# LightingUPS-AC.net
KiCad netlist of a schematic drawn in EAGLE
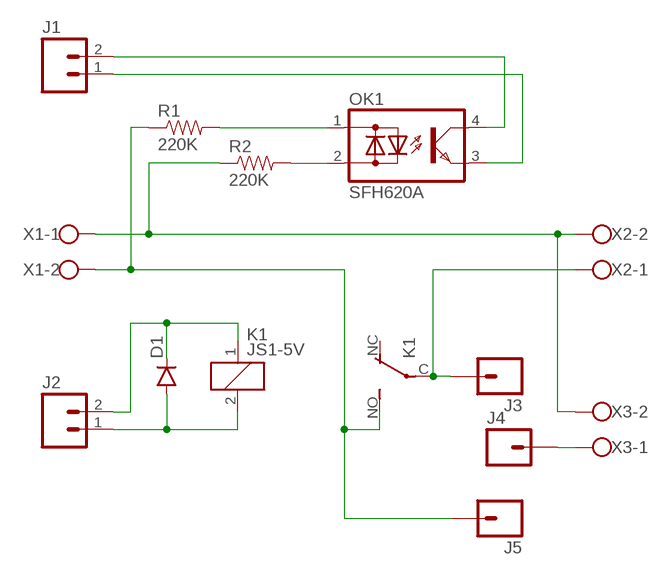
[diagram p0: schematic, sheet 1]

(export (version "E")
  (design (tool "Eeschema 10.0.6"))
  (components
    (comp (ref "D1")
      (value "DIODEPTH")
      (footprint "eagle-import:DIODE-1N4001")
      (libsource (lib "eagle-import") (part "DIODEPTH"))
    )
    (comp (ref "J1")
      (value "M02PTH")
      (footprint "eagle-import:1X02")
      (libsource (lib "eagle-import") (part "M02PTH"))
    )
    (comp (ref "J2")
      (value "M02PTH")
      (footprint "eagle-import:1X02")
      (libsource (lib "eagle-import") (part "M02PTH"))
    )
    (comp (ref "J3")
      (value "M01PTH")
      (footprint "eagle-import:1X01")
      (libsource (lib "eagle-import") (part "M01PTH"))
    )
    (comp (ref "J4")
      (value "M01PTH")
      (footprint "eagle-import:1X01")
      (libsource (lib "eagle-import") (part "M01PTH"))
    )
    (comp (ref "J5")
      (value "M01PTH")
      (footprint "eagle-import:1X01")
      (libsource (lib "eagle-import") (part "M01PTH"))
    )
    (comp (ref "K1")
      (value "JS1-5V")
      (footprint "eagle-import:JS-M")
      (libsource (lib "eagle-import") (part "JS-M1-9V-4"))
    )
    (comp (ref "OK1")
      (value "SFH620A")
      (footprint "eagle-import:DIL04")
      (fields (field (name "MPN") "SFH620A-2"))
      (libsource (lib "eagle-import") (part "SFH620A"))
    )
    (comp (ref "R1")
      (value "220K")
      (footprint "eagle-import:AXIAL-0.4")
      (libsource (lib "eagle-import") (part "RESISTORPTH-1/4W"))
    )
    (comp (ref "R2")
      (value "220K")
      (footprint "eagle-import:AXIAL-0.4")
      (libsource (lib "eagle-import") (part "RESISTORPTH-1/4W"))
    )
    (comp (ref "X1")
      (value "W237-102")
      (footprint "eagle-import:W237-102")
      (fields (field (name "MPN") "237-102"))
      (libsource (lib "eagle-import") (part "W237-102"))
    )
    (comp (ref "X2")
      (value "W237-102")
      (footprint "eagle-import:W237-102")
      (fields (field (name "MPN") "237-102"))
      (libsource (lib "eagle-import") (part "W237-102"))
    )
    (comp (ref "X3")
      (value "W237-102")
      (footprint "eagle-import:W237-102")
      (fields (field (name "MPN") "237-102"))
      (libsource (lib "eagle-import") (part "W237-102"))
    )
  )
  (nets
    (net (code "1") (name "Net-(D1-PadA)") (class "Default")
      (node (ref "D1") (pin "A") (pinfunction "A_A") (pintype "passive"))
      (node (ref "J2") (pin "1") (pinfunction "1_1") (pintype "passive"))
      (node (ref "K1") (pin "2") (pinfunction "2_2") (pintype "passive"))
    )
    (net (code "2") (name "Net-(D1-PadC)") (class "Default")
      (node (ref "D1") (pin "C") (pinfunction "C_C") (pintype "passive"))
      (node (ref "J2") (pin "2") (pinfunction "2_2") (pintype "passive"))
      (node (ref "K1") (pin "1") (pinfunction "1_1") (pintype "passive"))
    )
    (net (code "3") (name "Net-(K1B-P)") (class "Default")
      (node (ref "J3") (pin "1") (pinfunction "1_1") (pintype "passive"))
      (node (ref "K1") (pin "C") (pinfunction "P_C") (pintype "passive"))
      (node (ref "X2") (pin "1") (pinfunction "KL_1") (pintype "passive"))
    )
    (net (code "4") (name "Net-(K1B-S)") (class "Default")
      (node (ref "J5") (pin "1") (pinfunction "1_1") (pintype "passive"))
      (node (ref "K1") (pin "NO") (pinfunction "S_NO") (pintype "passive"))
      (node (ref "R1") (pin "P$1") (pinfunction "1_P$1") (pintype "passive"))
      (node (ref "X1") (pin "2") (pinfunction "KL_2") (pintype "passive"))
    )
    (net (code "5") (name "Net-(OK1-AC1)") (class "Default")
      (node (ref "OK1") (pin "1") (pinfunction "AC1_1") (pintype "passive"))
      (node (ref "R1") (pin "P$2") (pinfunction "2_P$2") (pintype "passive"))
    )
    (net (code "6") (name "Net-(OK1-AC2)") (class "Default")
      (node (ref "OK1") (pin "2") (pinfunction "AC2_2") (pintype "passive"))
      (node (ref "R2") (pin "P$2") (pinfunction "2_P$2") (pintype "passive"))
    )
    (net (code "7") (name "Net-(OK1-C)") (class "Default")
      (node (ref "J1") (pin "2") (pinfunction "2_2") (pintype "passive"))
      (node (ref "OK1") (pin "4") (pinfunction "C_4") (pintype "passive"))
    )
    (net (code "8") (name "Net-(OK1-E)") (class "Default")
      (node (ref "J1") (pin "1") (pinfunction "1_1") (pintype "passive"))
      (node (ref "OK1") (pin "3") (pinfunction "E_3") (pintype "passive"))
    )
    (net (code "9") (name "Net-(R2-1)") (class "Default")
      (node (ref "R2") (pin "P$1") (pinfunction "1_P$1") (pintype "passive"))
      (node (ref "X1") (pin "1") (pinfunction "KL_1") (pintype "passive"))
      (node (ref "X2") (pin "2") (pinfunction "KL_2") (pintype "passive"))
      (node (ref "X3") (pin "2") (pinfunction "KL_2") (pintype "passive"))
    )
    (net (code "10") (name "Net-(X3A-KL)") (class "Default")
      (node (ref "J4") (pin "1") (pinfunction "1_1") (pintype "passive"))
      (node (ref "X3") (pin "1") (pinfunction "KL_1") (pintype "passive"))
    )
    (net (code "11") (name "unconnected-(K1B-O-PadNC)") (class "Default")
      (node (ref "K1") (pin "NC") (pinfunction "O_NC") (pintype "passive"))
    )
  )
)
